# LMS.net
KiCad netlist of a schematic drawn in Altium Designer
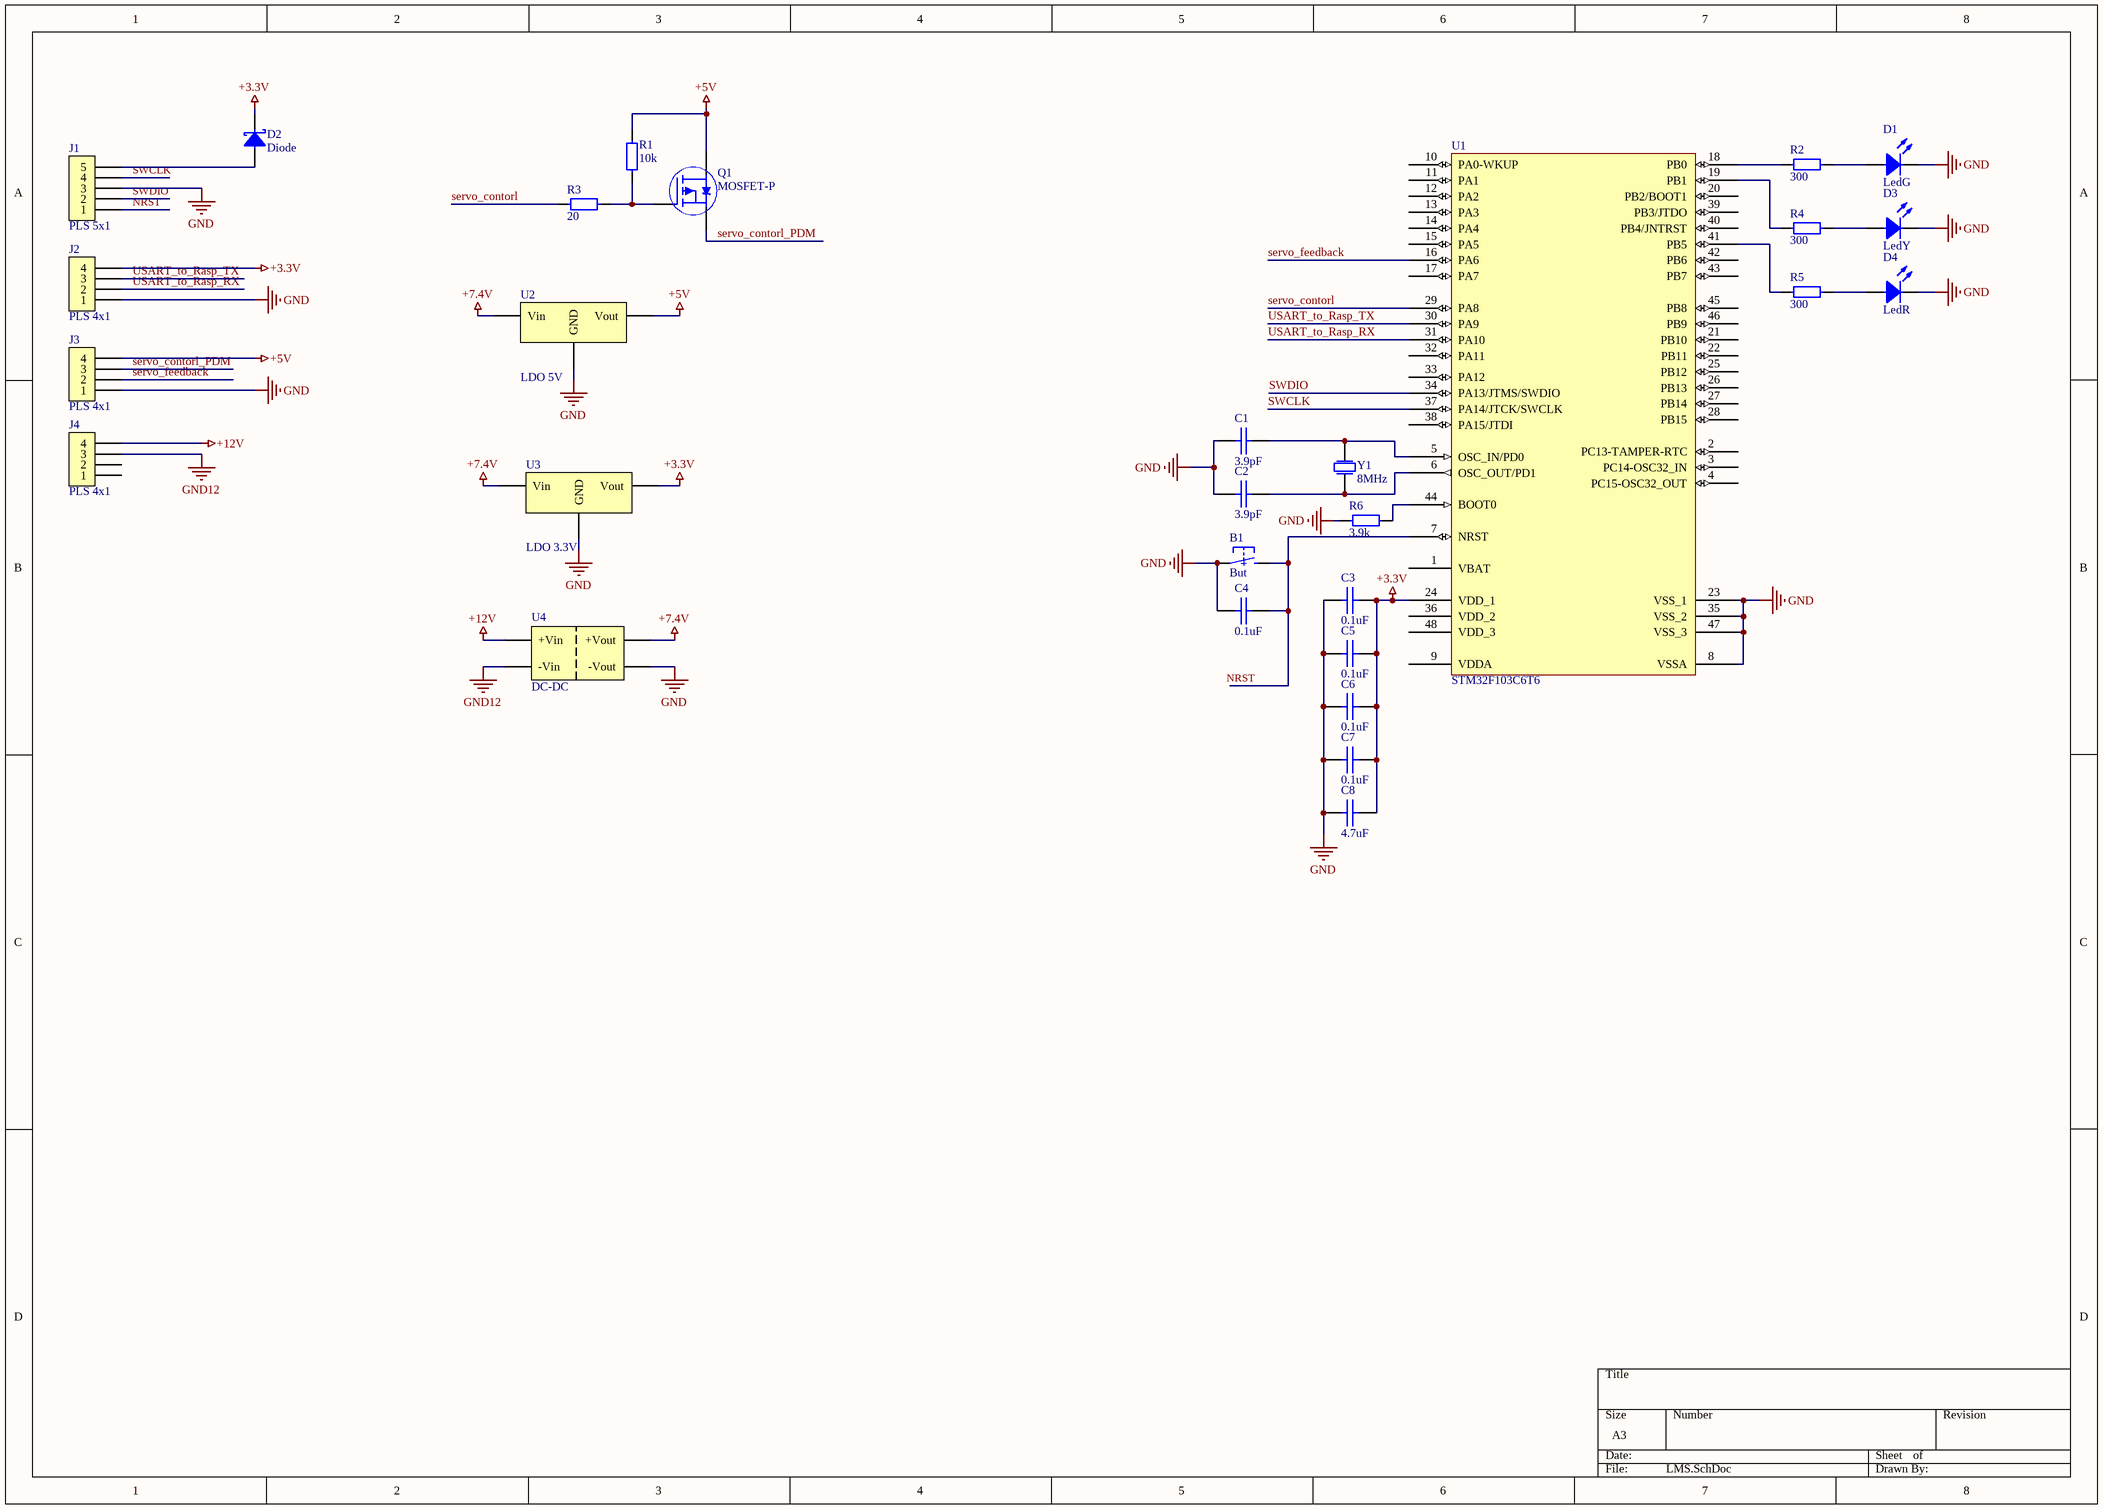
[diagram p0: LMS.SchDoc]

(export (version "E")
  (design (tool "Eeschema 10.0.6"))
  (components
    (comp (ref "B1")
      (value "But")
      (footprint "BUTTON 6x3.5")
      (description "Button 2 Conn SMD")
      (libsource (lib "RoboCor") (part "Button"))
    )
    (comp (ref "C1")
      (value "3.9pF")
      (footprint "0805 Capicator")
      (libsource (lib "RoboCor") (part "Cap 39pF"))
    )
    (comp (ref "C2")
      (value "3.9pF")
      (footprint "0805 Capicator")
      (libsource (lib "RoboCor") (part "Cap 39pF"))
    )
    (comp (ref "C3")
      (value "0.1uF")
      (footprint "0805 Capicator")
      (libsource (lib "RoboCor") (part "Cap 0.1uF"))
    )
    (comp (ref "C4")
      (value "0.1uF")
      (footprint "0805 Capicator")
      (libsource (lib "RoboCor") (part "Cap 0.1uF"))
    )
    (comp (ref "C5")
      (value "0.1uF")
      (footprint "0805 Capicator")
      (libsource (lib "RoboCor") (part "Cap 0.1uF"))
    )
    (comp (ref "C6")
      (value "0.1uF")
      (footprint "0805 Capicator")
      (libsource (lib "RoboCor") (part "Cap 0.1uF"))
    )
    (comp (ref "C7")
      (value "0.1uF")
      (footprint "0805 Capicator")
      (libsource (lib "RoboCor") (part "Cap 0.1uF"))
    )
    (comp (ref "C8")
      (value "4.7uF")
      (footprint "0805 Capicator")
      (libsource (lib "RoboCor") (part "Cap 4.7uF"))
    )
    (comp (ref "D1") (value "LedG") (footprint "0805 Led") (libsource (lib "RoboCor") (part "Led Green")))
    (comp (ref "D2")
      (value "Diode")
      (footprint "sod-123")
      (description "0.5 A, Low Forward Voltage less than 385 mV, 400 mW Power Dissipation Package")
      (libsource (lib "RoboCor") (part "Diode Schottky"))
    )
    (comp (ref "D3") (value "LedY") (footprint "0805 Led") (libsource (lib "RoboCor") (part "Led Yellow")))
    (comp (ref "D4") (value "LedR") (footprint "0805 Led") (libsource (lib "RoboCor") (part "Led Red")))
    (comp (ref "J1")
      (value "PLS 5x1")
      (footprint "PLS 5x1")
      (description "Header, 5-Pin")
      (libsource (lib "RoboCor") (part "Conn 5"))
    )
    (comp (ref "J2")
      (value "PLS 4x1")
      (footprint "PLS 4x1")
      (description "Header, 4-Pin")
      (libsource (lib "RoboCor") (part "Conn 4"))
    )
    (comp (ref "J3")
      (value "PLS 4x1")
      (footprint "PLS 4x1")
      (description "Header, 4-Pin")
      (libsource (lib "RoboCor") (part "Conn 4"))
    )
    (comp (ref "J4")
      (value "PLS 4x1")
      (footprint "PLS 4x1")
      (description "Header, 4-Pin")
      (libsource (lib "RoboCor") (part "Conn 4"))
    )
    (comp (ref "Q1")
      (value "MOSFET-P")
      (footprint "SOT-23")
      (description "P-Channel Power MOSFET 12V to 20V, Infineon")
      (libsource (lib "RoboCor") (part "MOSFET-P"))
    )
    (comp (ref "R1") (value "10k") (footprint "0805 Resistor") (libsource (lib "RoboCor") (part "Res 10k")))
    (comp (ref "R2") (value "300") (footprint "0805 Resistor") (libsource (lib "RoboCor") (part "Res 300")))
    (comp (ref "R3") (value "20") (footprint "0805 Resistor") (libsource (lib "RoboCor") (part "Res 20")))
    (comp (ref "R4") (value "300") (footprint "0805 Resistor") (libsource (lib "RoboCor") (part "Res 300")))
    (comp (ref "R5") (value "300") (footprint "0805 Resistor") (libsource (lib "RoboCor") (part "Res 300")))
    (comp (ref "R6") (value "3.9k") (footprint "0805 Resistor") (libsource (lib "RoboCor") (part "Res 3.9k")))
    (comp (ref "U1")
      (value "STM32F103C6T6")
      (footprint "STM32F103C6T6")
      (libsource (lib "RoboCor") (part "STM32F103C6T6"))
    )
    (comp (ref "U2")
      (value "LDO 5V")
      (footprint "TO-252")
      (description "LDO Regulator Pos 5V 1A")
      (libsource (lib "RoboCor") (part "LDO 5V"))
    )
    (comp (ref "U3")
      (value "LDO 3.3V")
      (footprint "SOT-223")
      (description "LDO Regulator Pos 3.3V 1.3A 4-Pin(3+Tab) SOT-223 T/R")
      (libsource (lib "RoboCor") (part "LDO 3.3V"))
    )
    (comp (ref "U4") (value "DC-DC") (footprint "DC-DC") (libsource (lib "RoboCor") (part "DC-DC")))
    (comp (ref "Y1")
      (value "8MHz")
      (footprint "hc-49sm")
      (description "Crystal. HC-49SM (US)")
      (libsource (lib "RoboCor") (part "Crystal 8MHz"))
    )
  )
  (nets
    (net (code "1") (name "+3.3V") (class "Default")
      (node (ref "C3") (pin "2") (pinfunction "2_2") (pintype "passive"))
      (node (ref "C5") (pin "2") (pinfunction "2_2") (pintype "passive"))
      (node (ref "C6") (pin "2") (pinfunction "2_2") (pintype "passive"))
      (node (ref "C7") (pin "2") (pinfunction "2_2") (pintype "passive"))
      (node (ref "C8") (pin "2") (pinfunction "2_2") (pintype "passive"))
      (node (ref "D2") (pin "2") (pinfunction "2_2") (pintype "passive"))
      (node (ref "J2") (pin "4") (pinfunction "4_4") (pintype "passive"))
      (node (ref "U1") (pin "24") (pinfunction "VDD_1_24") (pintype "power_in"))
      (node (ref "U3") (pin "2") (pinfunction "Vout_2") (pintype "power_in"))
    )
    (net (code "2") (name "+5V") (class "Default")
      (node (ref "J3") (pin "4") (pinfunction "4_4") (pintype "passive"))
      (node (ref "Q1") (pin "3") (pinfunction "Drain_3") (pintype "passive"))
      (node (ref "R1") (pin "2") (pinfunction "2_2") (pintype "passive"))
      (node (ref "U2") (pin "2") (pinfunction "Vout_2") (pintype "power_in"))
    )
    (net (code "3") (name "+7.4V") (class "Default")
      (node (ref "U2") (pin "3") (pinfunction "Vin_3") (pintype "power_in"))
      (node (ref "U3") (pin "3") (pinfunction "Vin_3") (pintype "power_in"))
      (node (ref "U4") (pin "3") (pinfunction "+Vout_3") (pintype "power_in"))
    )
    (net (code "4") (name "+12V") (class "Default")
      (node (ref "J4") (pin "4") (pinfunction "4_4") (pintype "passive"))
      (node (ref "U4") (pin "1") (pinfunction "+Vin_1") (pintype "power_in"))
    )
    (net (code "5") (name "/NRST") (class "Default")
      (node (ref "B1") (pin "2") (pinfunction "2_2") (pintype "passive"))
      (node (ref "C4") (pin "2") (pinfunction "2_2") (pintype "passive"))
      (node (ref "J1") (pin "1") (pinfunction "1_1") (pintype "passive"))
      (node (ref "U1") (pin "7") (pinfunction "NRST_7") (pintype "bidirectional"))
    )
    (net (code "6") (name "/SWCLK") (class "Default")
      (node (ref "J1") (pin "4") (pinfunction "4_4") (pintype "passive"))
      (node (ref "U1") (pin "37") (pinfunction "PA14/JTCK/SWCLK_37") (pintype "bidirectional"))
    )
    (net (code "7") (name "/SWDIO") (class "Default")
      (node (ref "J1") (pin "2") (pinfunction "2_2") (pintype "passive"))
      (node (ref "U1") (pin "34") (pinfunction "PA13/JTMS/SWDIO_34") (pintype "bidirectional"))
    )
    (net (code "8") (name "/USART_to_Rasp_RX") (class "Default")
      (node (ref "J2") (pin "2") (pinfunction "2_2") (pintype "passive"))
      (node (ref "U1") (pin "31") (pinfunction "PA10_31") (pintype "bidirectional"))
    )
    (net (code "9") (name "/USART_to_Rasp_TX") (class "Default")
      (node (ref "J2") (pin "3") (pinfunction "3_3") (pintype "passive"))
      (node (ref "U1") (pin "30") (pinfunction "PA9_30") (pintype "bidirectional"))
    )
    (net (code "10") (name "/servo_contorl") (class "Default")
      (node (ref "R3") (pin "1") (pinfunction "1_1") (pintype "passive"))
      (node (ref "U1") (pin "29") (pinfunction "PA8_29") (pintype "bidirectional"))
    )
    (net (code "11") (name "/servo_contorl_PDM") (class "Default")
      (node (ref "J3") (pin "3") (pinfunction "3_3") (pintype "passive"))
      (node (ref "Q1") (pin "2") (pinfunction "Source_2") (pintype "passive"))
    )
    (net (code "12") (name "/servo_feedback") (class "Default")
      (node (ref "J3") (pin "2") (pinfunction "2_2") (pintype "passive"))
      (node (ref "U1") (pin "16") (pinfunction "PA6_16") (pintype "bidirectional"))
    )
    (net (code "13") (name "GND") (class "Default")
      (node (ref "B1") (pin "1") (pinfunction "1_1") (pintype "passive"))
      (node (ref "C1") (pin "1") (pinfunction "1_1") (pintype "passive"))
      (node (ref "C2") (pin "1") (pinfunction "1_1") (pintype "passive"))
      (node (ref "C3") (pin "1") (pinfunction "1_1") (pintype "passive"))
      (node (ref "C4") (pin "1") (pinfunction "1_1") (pintype "passive"))
      (node (ref "C5") (pin "1") (pinfunction "1_1") (pintype "passive"))
      (node (ref "C6") (pin "1") (pinfunction "1_1") (pintype "passive"))
      (node (ref "C7") (pin "1") (pinfunction "1_1") (pintype "passive"))
      (node (ref "C8") (pin "1") (pinfunction "1_1") (pintype "passive"))
      (node (ref "D1") (pin "2") (pinfunction "2_2") (pintype "passive"))
      (node (ref "D3") (pin "2") (pinfunction "2_2") (pintype "passive"))
      (node (ref "D4") (pin "2") (pinfunction "2_2") (pintype "passive"))
      (node (ref "J1") (pin "3") (pinfunction "3_3") (pintype "passive"))
      (node (ref "J2") (pin "1") (pinfunction "1_1") (pintype "passive"))
      (node (ref "J3") (pin "1") (pinfunction "1_1") (pintype "passive"))
      (node (ref "R6") (pin "1") (pinfunction "1_1") (pintype "passive"))
      (node (ref "U1") (pin "23") (pinfunction "VSS_1_23") (pintype "power_in"))
      (node (ref "U1") (pin "35") (pinfunction "VSS_2_35") (pintype "power_in"))
      (node (ref "U1") (pin "47") (pinfunction "VSS_3_47") (pintype "power_in"))
      (node (ref "U1") (pin "8") (pinfunction "VSSA_8") (pintype "power_in"))
      (node (ref "U2") (pin "1") (pinfunction "GND_1") (pintype "power_in"))
      (node (ref "U3") (pin "1") (pinfunction "GND_1") (pintype "power_in"))
      (node (ref "U4") (pin "4") (pinfunction "-Vout_4") (pintype "power_in"))
    )
    (net (code "14") (name "GND12") (class "Default")
      (node (ref "J4") (pin "3") (pinfunction "3_3") (pintype "passive"))
      (node (ref "U4") (pin "2") (pinfunction "-Vin_2") (pintype "power_in"))
    )
    (net (code "15") (name "Net-(D1-Pad1)") (class "Default")
      (node (ref "D1") (pin "1") (pinfunction "1_1") (pintype "passive"))
      (node (ref "R2") (pin "2") (pinfunction "2_2") (pintype "passive"))
    )
    (net (code "16") (name "Net-(D2-Pad1)") (class "Default")
      (node (ref "D2") (pin "1") (pinfunction "1_1") (pintype "passive"))
      (node (ref "J1") (pin "5") (pinfunction "5_5") (pintype "passive"))
    )
    (net (code "17") (name "Net-(D3-Pad1)") (class "Default")
      (node (ref "D3") (pin "1") (pinfunction "1_1") (pintype "passive"))
      (node (ref "R4") (pin "2") (pinfunction "2_2") (pintype "passive"))
    )
    (net (code "18") (name "Net-(D4-Pad1)") (class "Default")
      (node (ref "D4") (pin "1") (pinfunction "1_1") (pintype "passive"))
      (node (ref "R5") (pin "2") (pinfunction "2_2") (pintype "passive"))
    )
    (net (code "19") (name "Net-(Q1-Gate)") (class "Default")
      (node (ref "Q1") (pin "1") (pinfunction "Gate_1") (pintype "passive"))
      (node (ref "R1") (pin "1") (pinfunction "1_1") (pintype "passive"))
      (node (ref "R3") (pin "2") (pinfunction "2_2") (pintype "passive"))
    )
    (net (code "20") (name "Net-(U1-BOOT0)") (class "Default")
      (node (ref "R6") (pin "2") (pinfunction "2_2") (pintype "passive"))
      (node (ref "U1") (pin "44") (pinfunction "BOOT0_44") (pintype "input"))
    )
    (net (code "21") (name "Net-(U1-OSC_IN{slash}PD0)") (class "Default")
      (node (ref "C1") (pin "2") (pinfunction "2_2") (pintype "passive"))
      (node (ref "U1") (pin "5") (pinfunction "OSC_IN/PD0_5") (pintype "input"))
      (node (ref "Y1") (pin "2") (pinfunction "2_2") (pintype "passive"))
    )
    (net (code "22") (name "Net-(U1-OSC_OUT{slash}PD1)") (class "Default")
      (node (ref "C2") (pin "2") (pinfunction "2_2") (pintype "passive"))
      (node (ref "U1") (pin "6") (pinfunction "OSC_OUT/PD1_6") (pintype "output"))
      (node (ref "Y1") (pin "1") (pinfunction "1_1") (pintype "passive"))
    )
    (net (code "23") (name "Net-(U1-PB0)") (class "Default")
      (node (ref "R2") (pin "1") (pinfunction "1_1") (pintype "passive"))
      (node (ref "U1") (pin "18") (pinfunction "PB0_18") (pintype "bidirectional"))
    )
    (net (code "24") (name "Net-(U1-PB1)") (class "Default")
      (node (ref "R4") (pin "1") (pinfunction "1_1") (pintype "passive"))
      (node (ref "U1") (pin "19") (pinfunction "PB1_19") (pintype "bidirectional"))
    )
    (net (code "25") (name "Net-(U1-PB5)") (class "Default")
      (node (ref "R5") (pin "1") (pinfunction "1_1") (pintype "passive"))
      (node (ref "U1") (pin "41") (pinfunction "PB5_41") (pintype "bidirectional"))
    )
    (net (code "26") (name "unconnected-(J4-Pad1)") (class "Default")
      (node (ref "J4") (pin "1") (pinfunction "1_1") (pintype "passive"))
    )
    (net (code "27") (name "unconnected-(J4-Pad2)") (class "Default")
      (node (ref "J4") (pin "2") (pinfunction "2_2") (pintype "passive"))
    )
    (net (code "28") (name "unconnected-(U1-PA0-WKUP-Pad10)") (class "Default")
      (node (ref "U1") (pin "10") (pinfunction "PA0-WKUP_10") (pintype "bidirectional"))
    )
    (net (code "29") (name "unconnected-(U1-PA1-Pad11)") (class "Default")
      (node (ref "U1") (pin "11") (pinfunction "PA1_11") (pintype "bidirectional"))
    )
    (net (code "30") (name "unconnected-(U1-PA2-Pad12)") (class "Default")
      (node (ref "U1") (pin "12") (pinfunction "PA2_12") (pintype "bidirectional"))
    )
    (net (code "31") (name "unconnected-(U1-PA3-Pad13)") (class "Default")
      (node (ref "U1") (pin "13") (pinfunction "PA3_13") (pintype "bidirectional"))
    )
    (net (code "32") (name "unconnected-(U1-PA4-Pad14)") (class "Default")
      (node (ref "U1") (pin "14") (pinfunction "PA4_14") (pintype "bidirectional"))
    )
    (net (code "33") (name "unconnected-(U1-PA5-Pad15)") (class "Default")
      (node (ref "U1") (pin "15") (pinfunction "PA5_15") (pintype "bidirectional"))
    )
    (net (code "34") (name "unconnected-(U1-PA7-Pad17)") (class "Default")
      (node (ref "U1") (pin "17") (pinfunction "PA7_17") (pintype "bidirectional"))
    )
    (net (code "35") (name "unconnected-(U1-PA11-Pad32)") (class "Default")
      (node (ref "U1") (pin "32") (pinfunction "PA11_32") (pintype "bidirectional"))
    )
    (net (code "36") (name "unconnected-(U1-PA12-Pad33)") (class "Default")
      (node (ref "U1") (pin "33") (pinfunction "PA12_33") (pintype "bidirectional"))
    )
    (net (code "37") (name "unconnected-(U1-PA15{slash}JTDI-Pad38)") (class "Default")
      (node (ref "U1") (pin "38") (pinfunction "PA15/JTDI_38") (pintype "bidirectional"))
    )
    (net (code "38") (name "unconnected-(U1-PB2{slash}BOOT1-Pad20)") (class "Default")
      (node (ref "U1") (pin "20") (pinfunction "PB2/BOOT1_20") (pintype "bidirectional"))
    )
    (net (code "39") (name "unconnected-(U1-PB3{slash}JTDO-Pad39)") (class "Default")
      (node (ref "U1") (pin "39") (pinfunction "PB3/JTDO_39") (pintype "bidirectional"))
    )
    (net (code "40") (name "unconnected-(U1-PB4{slash}JNTRST-Pad40)") (class "Default")
      (node (ref "U1") (pin "40") (pinfunction "PB4/JNTRST_40") (pintype "bidirectional"))
    )
    (net (code "41") (name "unconnected-(U1-PB6-Pad42)") (class "Default")
      (node (ref "U1") (pin "42") (pinfunction "PB6_42") (pintype "bidirectional"))
    )
    (net (code "42") (name "unconnected-(U1-PB7-Pad43)") (class "Default")
      (node (ref "U1") (pin "43") (pinfunction "PB7_43") (pintype "bidirectional"))
    )
    (net (code "43") (name "unconnected-(U1-PB8-Pad45)") (class "Default")
      (node (ref "U1") (pin "45") (pinfunction "PB8_45") (pintype "bidirectional"))
    )
    (net (code "44") (name "unconnected-(U1-PB9-Pad46)") (class "Default")
      (node (ref "U1") (pin "46") (pinfunction "PB9_46") (pintype "bidirectional"))
    )
    (net (code "45") (name "unconnected-(U1-PB10-Pad21)") (class "Default")
      (node (ref "U1") (pin "21") (pinfunction "PB10_21") (pintype "bidirectional"))
    )
    (net (code "46") (name "unconnected-(U1-PB11-Pad22)") (class "Default")
      (node (ref "U1") (pin "22") (pinfunction "PB11_22") (pintype "bidirectional"))
    )
    (net (code "47") (name "unconnected-(U1-PB12-Pad25)") (class "Default")
      (node (ref "U1") (pin "25") (pinfunction "PB12_25") (pintype "bidirectional"))
    )
    (net (code "48") (name "unconnected-(U1-PB13-Pad26)") (class "Default")
      (node (ref "U1") (pin "26") (pinfunction "PB13_26") (pintype "bidirectional"))
    )
    (net (code "49") (name "unconnected-(U1-PB14-Pad27)") (class "Default")
      (node (ref "U1") (pin "27") (pinfunction "PB14_27") (pintype "bidirectional"))
    )
    (net (code "50") (name "unconnected-(U1-PB15-Pad28)") (class "Default")
      (node (ref "U1") (pin "28") (pinfunction "PB15_28") (pintype "bidirectional"))
    )
    (net (code "51") (name "unconnected-(U1-PC13-TAMPER-RTC-Pad2)") (class "Default")
      (node (ref "U1") (pin "2") (pinfunction "PC13-TAMPER-RTC_2") (pintype "bidirectional"))
    )
    (net (code "52") (name "unconnected-(U1-PC14-OSC32_IN-Pad3)") (class "Default")
      (node (ref "U1") (pin "3") (pinfunction "PC14-OSC32_IN_3") (pintype "bidirectional"))
    )
    (net (code "53") (name "unconnected-(U1-PC15-OSC32_OUT-Pad4)") (class "Default")
      (node (ref "U1") (pin "4") (pinfunction "PC15-OSC32_OUT_4") (pintype "bidirectional"))
    )
    (net (code "54") (name "unconnected-(U1-VBAT-Pad1)") (class "Default")
      (node (ref "U1") (pin "1") (pinfunction "VBAT_1") (pintype "power_in"))
    )
    (net (code "55") (name "unconnected-(U1-VDDA-Pad9)") (class "Default")
      (node (ref "U1") (pin "9") (pinfunction "VDDA_9") (pintype "power_in"))
    )
    (net (code "56") (name "unconnected-(U1-VDD_2-Pad36)") (class "Default")
      (node (ref "U1") (pin "36") (pinfunction "VDD_2_36") (pintype "power_in"))
    )
    (net (code "57") (name "unconnected-(U1-VDD_3-Pad48)") (class "Default")
      (node (ref "U1") (pin "48") (pinfunction "VDD_3_48") (pintype "power_in"))
    )
  )
)
